# CW308T_PSoC62_UFO.net
KiCad netlist of a schematic drawn in Altium Designer
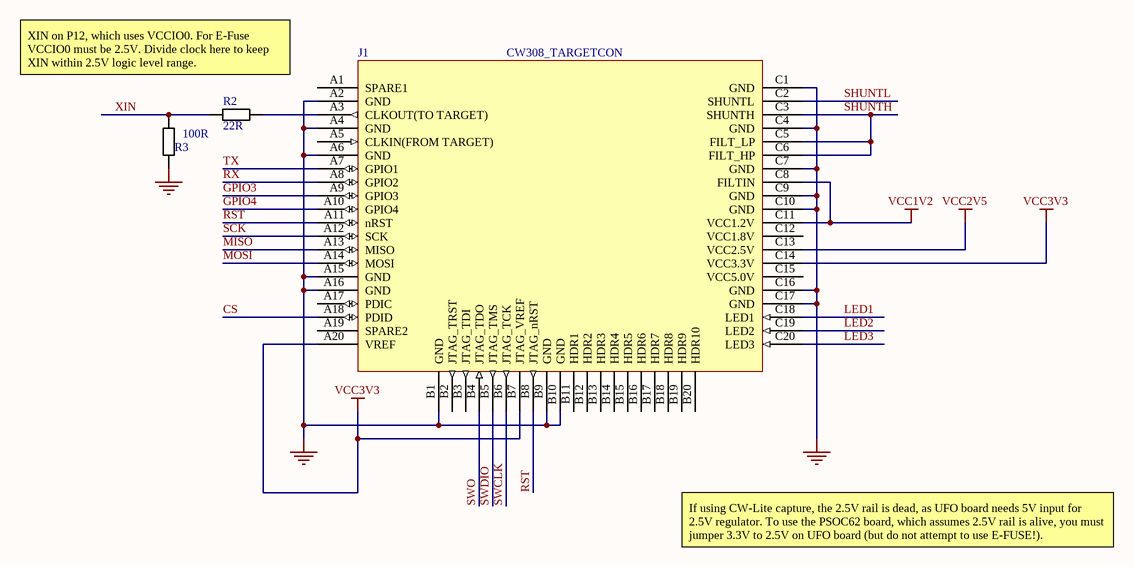
[diagram p0: CW308T_PSoC62_UFO.SchDoc]

(export (version "E")
  (design (tool "Eeschema 10.0.6"))
  (components
    (comp (ref "J1")
      (value "CW308_TARGETCON")
      (footprint "CW308_TBOARD_CONN")
      (description "CW308 \"Standard\" Target Board Connector")
      (fields (field (name "PART NUMBER") "CW308_TBOARD"))
      (libsource (lib "NewAE_AltiumLib") (part "CW308_TBOARD"))
    )
    (comp (ref "R2")
      (value "22R")
      (footprint "RESC1608X55N")
      (description "22R res, 0603, 1%, 1/10W")
      (fields (field (name "PART NUMBER") "RCHIP-22R-0603") (field (name "TOLERANCE") "1%"))
      (libsource (lib "") (part "RES-EU_1"))
    )
    (comp (ref "R3")
      (value "100R")
      (footprint "RESC1608X55N")
      (description "100R res, 0603, 1%, 1/10W")
      (fields (field (name "PART NUMBER") "RCHIP-100R-0603") (field (name "TOLERANCE") "1%"))
      (libsource (lib "NewAE_AltiumLib") (part "RES-EU"))
    )
  )
  (nets
    (net (code "1") (name "/CS") (class "Default")
      (node (ref "J1") (pin "A18") (pinfunction "PDID_A18") (pintype "bidirectional"))
    )
    (net (code "2") (name "/GPIO3") (class "Default")
      (node (ref "J1") (pin "A9") (pinfunction "GPIO3_A9") (pintype "bidirectional"))
    )
    (net (code "3") (name "/GPIO4") (class "Default")
      (node (ref "J1") (pin "A10") (pinfunction "GPIO4_A10") (pintype "bidirectional"))
    )
    (net (code "4") (name "/LED1") (class "Default")
      (node (ref "J1") (pin "C18") (pinfunction "LED1_C18") (pintype "input"))
    )
    (net (code "5") (name "/LED2") (class "Default")
      (node (ref "J1") (pin "C19") (pinfunction "LED2_C19") (pintype "input"))
    )
    (net (code "6") (name "/LED3") (class "Default")
      (node (ref "J1") (pin "C20") (pinfunction "LED3_C20") (pintype "input"))
    )
    (net (code "7") (name "/MISO") (class "Default")
      (node (ref "J1") (pin "A13") (pinfunction "MISO_A13") (pintype "bidirectional"))
    )
    (net (code "8") (name "/MOSI") (class "Default")
      (node (ref "J1") (pin "A14") (pinfunction "MOSI_A14") (pintype "bidirectional"))
    )
    (net (code "9") (name "/RST") (class "Default")
      (node (ref "J1") (pin "A11") (pinfunction "nRST_A11") (pintype "bidirectional"))
      (node (ref "J1") (pin "B8") (pinfunction "JTAG_nRST_B8") (pintype "output"))
    )
    (net (code "10") (name "/RX") (class "Default")
      (node (ref "J1") (pin "A8") (pinfunction "GPIO2_A8") (pintype "bidirectional"))
    )
    (net (code "11") (name "/SCK") (class "Default")
      (node (ref "J1") (pin "A12") (pinfunction "SCK_A12") (pintype "bidirectional"))
    )
    (net (code "12") (name "/SHUNTH") (class "Default")
      (node (ref "J1") (pin "C3") (pinfunction "SHUNTH_C3") (pintype "passive"))
      (node (ref "J1") (pin "C5") (pinfunction "FILT_LP_C5") (pintype "passive"))
      (node (ref "J1") (pin "C6") (pinfunction "FILT_HP_C6") (pintype "passive"))
    )
    (net (code "13") (name "/SHUNTL") (class "Default")
      (node (ref "J1") (pin "C2") (pinfunction "SHUNTL_C2") (pintype "passive"))
    )
    (net (code "14") (name "/SWCLK") (class "Default")
      (node (ref "J1") (pin "B6") (pinfunction "JTAG_TCK_B6") (pintype "output"))
    )
    (net (code "15") (name "/SWDIO") (class "Default")
      (node (ref "J1") (pin "B5") (pinfunction "JTAG_TMS_B5") (pintype "output"))
    )
    (net (code "16") (name "/SWO") (class "Default")
      (node (ref "J1") (pin "B4") (pinfunction "JTAG_TDO_B4") (pintype "input"))
    )
    (net (code "17") (name "/TX") (class "Default")
      (node (ref "J1") (pin "A7") (pinfunction "GPIO1_A7") (pintype "bidirectional"))
    )
    (net (code "18") (name "/XIN") (class "Default")
      (node (ref "R2") (pin "1") (pinfunction "1_1") (pintype "passive"))
      (node (ref "R3") (pin "2") (pinfunction "2_2") (pintype "passive"))
    )
    (net (code "19") (name "GND") (class "Default")
      (node (ref "J1") (pin "A15") (pinfunction "GND_A15") (pintype "passive"))
      (node (ref "J1") (pin "A16") (pinfunction "GND_A16") (pintype "passive"))
      (node (ref "J1") (pin "A2") (pinfunction "GND_A2") (pintype "passive"))
      (node (ref "J1") (pin "A4") (pinfunction "GND_A4") (pintype "passive"))
      (node (ref "J1") (pin "A6") (pinfunction "GND_A6") (pintype "power_in"))
      (node (ref "J1") (pin "B1") (pinfunction "GND_B1") (pintype "passive"))
      (node (ref "J1") (pin "B10") (pinfunction "GND_B10") (pintype "passive"))
      (node (ref "J1") (pin "B9") (pinfunction "GND_B9") (pintype "passive"))
      (node (ref "J1") (pin "C1") (pinfunction "GND_C1") (pintype "power_in"))
      (node (ref "J1") (pin "C10") (pinfunction "GND_C10") (pintype "power_in"))
      (node (ref "J1") (pin "C16") (pinfunction "GND_C16") (pintype "power_in"))
      (node (ref "J1") (pin "C17") (pinfunction "GND_C17") (pintype "power_in"))
      (node (ref "J1") (pin "C4") (pinfunction "GND_C4") (pintype "power_in"))
      (node (ref "J1") (pin "C7") (pinfunction "GND_C7") (pintype "power_in"))
      (node (ref "J1") (pin "C9") (pinfunction "GND_C9") (pintype "power_in"))
      (node (ref "R3") (pin "1") (pinfunction "1_1") (pintype "passive"))
    )
    (net (code "20") (name "Net-(J1-CLKOUT(TO_TARGET))") (class "Default")
      (node (ref "J1") (pin "A3") (pinfunction "CLKOUT(TO_TARGET)_A3") (pintype "output"))
      (node (ref "R2") (pin "2") (pinfunction "2_2") (pintype "passive"))
    )
    (net (code "21") (name "VCC1V2") (class "Default")
      (node (ref "J1") (pin "C11") (pinfunction "VCC1.2V_C11") (pintype "power_in"))
      (node (ref "J1") (pin "C8") (pinfunction "FILTIN_C8") (pintype "passive"))
    )
    (net (code "22") (name "VCC2V5") (class "Default")
      (node (ref "J1") (pin "C13") (pinfunction "VCC2.5V_C13") (pintype "power_in"))
    )
    (net (code "23") (name "VCC3V3") (class "Default")
      (node (ref "J1") (pin "A20") (pinfunction "VREF_A20") (pintype "tri_state"))
      (node (ref "J1") (pin "B7") (pinfunction "JTAG_VREF_B7") (pintype "tri_state"))
      (node (ref "J1") (pin "C14") (pinfunction "VCC3.3V_C14") (pintype "power_in"))
    )
    (net (code "24") (name "unconnected-(J1-CLKIN(FROM_TARGET)-PadA5)") (class "Default")
      (node (ref "J1") (pin "A5") (pinfunction "CLKIN(FROM_TARGET)_A5") (pintype "input"))
    )
    (net (code "25") (name "unconnected-(J1-HDR1-PadB11)") (class "Default")
      (node (ref "J1") (pin "B11") (pinfunction "HDR1_B11") (pintype "passive"))
    )
    (net (code "26") (name "unconnected-(J1-HDR2-PadB12)") (class "Default")
      (node (ref "J1") (pin "B12") (pinfunction "HDR2_B12") (pintype "passive"))
    )
    (net (code "27") (name "unconnected-(J1-HDR3-PadB13)") (class "Default")
      (node (ref "J1") (pin "B13") (pinfunction "HDR3_B13") (pintype "passive"))
    )
    (net (code "28") (name "unconnected-(J1-HDR4-PadB14)") (class "Default")
      (node (ref "J1") (pin "B14") (pinfunction "HDR4_B14") (pintype "passive"))
    )
    (net (code "29") (name "unconnected-(J1-HDR5-PadB15)") (class "Default")
      (node (ref "J1") (pin "B15") (pinfunction "HDR5_B15") (pintype "passive"))
    )
    (net (code "30") (name "unconnected-(J1-HDR6-PadB16)") (class "Default")
      (node (ref "J1") (pin "B16") (pinfunction "HDR6_B16") (pintype "passive"))
    )
    (net (code "31") (name "unconnected-(J1-HDR7-PadB17)") (class "Default")
      (node (ref "J1") (pin "B17") (pinfunction "HDR7_B17") (pintype "passive"))
    )
    (net (code "32") (name "unconnected-(J1-HDR8-PadB18)") (class "Default")
      (node (ref "J1") (pin "B18") (pinfunction "HDR8_B18") (pintype "passive"))
    )
    (net (code "33") (name "unconnected-(J1-HDR9-PadB19)") (class "Default")
      (node (ref "J1") (pin "B19") (pinfunction "HDR9_B19") (pintype "passive"))
    )
    (net (code "34") (name "unconnected-(J1-HDR10-PadB20)") (class "Default")
      (node (ref "J1") (pin "B20") (pinfunction "HDR10_B20") (pintype "passive"))
    )
    (net (code "35") (name "unconnected-(J1-JTAG_TDI-PadB3)") (class "Default")
      (node (ref "J1") (pin "B3") (pinfunction "JTAG_TDI_B3") (pintype "output"))
    )
    (net (code "36") (name "unconnected-(J1-JTAG_TRST-PadB2)") (class "Default")
      (node (ref "J1") (pin "B2") (pinfunction "JTAG_TRST_B2") (pintype "output"))
    )
    (net (code "37") (name "unconnected-(J1-PDIC-PadA17)") (class "Default")
      (node (ref "J1") (pin "A17") (pinfunction "PDIC_A17") (pintype "bidirectional"))
    )
    (net (code "38") (name "unconnected-(J1-SPARE1-PadA1)") (class "Default")
      (node (ref "J1") (pin "A1") (pinfunction "SPARE1_A1") (pintype "passive"))
    )
    (net (code "39") (name "unconnected-(J1-SPARE2-PadA19)") (class "Default")
      (node (ref "J1") (pin "A19") (pinfunction "SPARE2_A19") (pintype "passive"))
    )
    (net (code "40") (name "unconnected-(J1-VCC1.8V-PadC12)") (class "Default")
      (node (ref "J1") (pin "C12") (pinfunction "VCC1.8V_C12") (pintype "power_in"))
    )
    (net (code "41") (name "unconnected-(J1-VCC5.0V-PadC15)") (class "Default")
      (node (ref "J1") (pin "C15") (pinfunction "VCC5.0V_C15") (pintype "power_in"))
    )
  )
)
